# RPI_3.net
KiCad netlist of a schematic drawn in Altium Designer
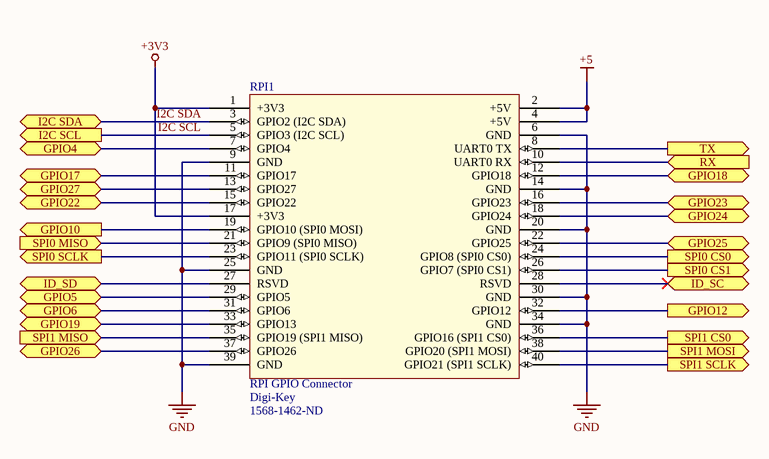
[diagram p0: RPI 3.SchDoc]

(export (version "E")
  (design (tool "Eeschema 10.0.6"))
  (components
    (comp (ref "RPI1")
      (value "RPI GPIO Connector")
      (footprint "rpi")
      (description "GPIO Header for Raspberry Pi A+/B+/Pi 2/Pi 3 - 2x20")
      (fields
        (field (name "MANUFACTURER") "SparkFun Electronics")
        (field (name "MANUFACTURER PART NUMBER") "PRT-14017")
        (field (name "SUPPLIER 1") "Digi-Key")
        (field (name "SUPPLIER PART NUMBER 1") "1568-1462-ND")
      )
      (libsource (lib "rpi") (part "rpi connector"))
    )
  )
  (nets
    (net (code "1") (name "+3V3") (class "Default")
      (node (ref "RPI1") (pin "1") (pinfunction "+3V3_1") (pintype "power_in"))
      (node (ref "RPI1") (pin "17") (pinfunction "+3V3_17") (pintype "power_in"))
    )
    (net (code "2") (name "+5") (class "Default")
      (node (ref "RPI1") (pin "2") (pinfunction "+5V_2") (pintype "power_in"))
      (node (ref "RPI1") (pin "4") (pinfunction "+5V_4") (pintype "power_in"))
    )
    (net (code "3") (name "/GPIO4") (class "Default")
      (node (ref "RPI1") (pin "7") (pinfunction "GPIO4_7") (pintype "bidirectional"))
    )
    (net (code "4") (name "/GPIO5") (class "Default")
      (node (ref "RPI1") (pin "29") (pinfunction "GPIO5_29") (pintype "bidirectional"))
    )
    (net (code "5") (name "/GPIO6") (class "Default")
      (node (ref "RPI1") (pin "31") (pinfunction "GPIO6_31") (pintype "bidirectional"))
    )
    (net (code "6") (name "/GPIO10") (class "Default")
      (node (ref "RPI1") (pin "19") (pinfunction "GPIO10_(SPI0_MOSI)_19") (pintype "bidirectional"))
    )
    (net (code "7") (name "/GPIO12") (class "Default")
      (node (ref "RPI1") (pin "32") (pinfunction "GPIO12_32") (pintype "bidirectional"))
    )
    (net (code "8") (name "/GPIO17") (class "Default")
      (node (ref "RPI1") (pin "11") (pinfunction "GPIO17_11") (pintype "bidirectional"))
    )
    (net (code "9") (name "/GPIO18") (class "Default")
      (node (ref "RPI1") (pin "12") (pinfunction "GPIO18_12") (pintype "bidirectional"))
    )
    (net (code "10") (name "/GPIO19") (class "Default")
      (node (ref "RPI1") (pin "33") (pinfunction "GPIO13_33") (pintype "bidirectional"))
    )
    (net (code "11") (name "/GPIO22") (class "Default")
      (node (ref "RPI1") (pin "15") (pinfunction "GPIO22_15") (pintype "bidirectional"))
    )
    (net (code "12") (name "/GPIO23") (class "Default")
      (node (ref "RPI1") (pin "16") (pinfunction "GPIO23_16") (pintype "bidirectional"))
    )
    (net (code "13") (name "/GPIO24") (class "Default")
      (node (ref "RPI1") (pin "18") (pinfunction "GPIO24_18") (pintype "bidirectional"))
    )
    (net (code "14") (name "/GPIO25") (class "Default")
      (node (ref "RPI1") (pin "22") (pinfunction "GPIO25_22") (pintype "bidirectional"))
    )
    (net (code "15") (name "/GPIO26") (class "Default")
      (node (ref "RPI1") (pin "37") (pinfunction "GPIO26_37") (pintype "bidirectional"))
    )
    (net (code "16") (name "/GPIO27") (class "Default")
      (node (ref "RPI1") (pin "13") (pinfunction "GPIO27_13") (pintype "bidirectional"))
    )
    (net (code "17") (name "/I2C SCL") (class "Default")
      (node (ref "RPI1") (pin "5") (pinfunction "GPIO3_(I2C_SCL)_5") (pintype "bidirectional"))
    )
    (net (code "18") (name "/I2C SDA") (class "Default")
      (node (ref "RPI1") (pin "3") (pinfunction "GPIO2_(I2C_SDA)_3") (pintype "bidirectional"))
    )
    (net (code "19") (name "/ID_SC") (class "Default")
      (node (ref "RPI1") (pin "28") (pinfunction "RSVD_28") (pintype "passive+no_connect"))
    )
    (net (code "20") (name "/ID_SD") (class "Default")
      (node (ref "RPI1") (pin "27") (pinfunction "RSVD_27") (pintype "passive"))
    )
    (net (code "21") (name "/RX") (class "Default")
      (node (ref "RPI1") (pin "10") (pinfunction "UART0_RX_10") (pintype "bidirectional"))
    )
    (net (code "22") (name "/SPI0 CS0") (class "Default")
      (node (ref "RPI1") (pin "24") (pinfunction "GPIO8_(SPI0_CS0)_24") (pintype "bidirectional"))
    )
    (net (code "23") (name "/SPI0 CS1") (class "Default")
      (node (ref "RPI1") (pin "26") (pinfunction "GPIO7_(SPI0_CS1)_26") (pintype "bidirectional"))
    )
    (net (code "24") (name "/SPI0 MISO") (class "Default")
      (node (ref "RPI1") (pin "21") (pinfunction "GPIO9_(SPI0_MISO)_21") (pintype "bidirectional"))
    )
    (net (code "25") (name "/SPI0 SCLK") (class "Default")
      (node (ref "RPI1") (pin "23") (pinfunction "GPIO11_(SPI0_SCLK)_23") (pintype "bidirectional"))
    )
    (net (code "26") (name "/SPI1 CS0") (class "Default")
      (node (ref "RPI1") (pin "36") (pinfunction "GPIO16_(SPI1_CS0)_36") (pintype "bidirectional"))
    )
    (net (code "27") (name "/SPI1 MISO") (class "Default")
      (node (ref "RPI1") (pin "35") (pinfunction "GPIO19_(SPI1_MISO)_35") (pintype "bidirectional"))
    )
    (net (code "28") (name "/SPI1 MOSI") (class "Default")
      (node (ref "RPI1") (pin "38") (pinfunction "GPIO20_(SPI1_MOSI)_38") (pintype "bidirectional"))
    )
    (net (code "29") (name "/SPI1 SCLK") (class "Default")
      (node (ref "RPI1") (pin "40") (pinfunction "GPIO21_(SPI1_SCLK)_40") (pintype "bidirectional"))
    )
    (net (code "30") (name "/TX") (class "Default")
      (node (ref "RPI1") (pin "8") (pinfunction "UART0_TX_8") (pintype "bidirectional"))
    )
    (net (code "31") (name "GND") (class "Default")
      (node (ref "RPI1") (pin "14") (pinfunction "GND_14") (pintype "power_in"))
      (node (ref "RPI1") (pin "20") (pinfunction "GND_20") (pintype "power_in"))
      (node (ref "RPI1") (pin "25") (pinfunction "GND_25") (pintype "power_in"))
      (node (ref "RPI1") (pin "30") (pinfunction "GND_30") (pintype "power_in"))
      (node (ref "RPI1") (pin "34") (pinfunction "GND_34") (pintype "passive"))
      (node (ref "RPI1") (pin "39") (pinfunction "GND_39") (pintype "power_in"))
      (node (ref "RPI1") (pin "6") (pinfunction "GND_6") (pintype "power_in"))
      (node (ref "RPI1") (pin "9") (pinfunction "GND_9") (pintype "power_in"))
    )
  )
)
